# Mixer.net
KiCad netlist of a schematic drawn in EAGLE
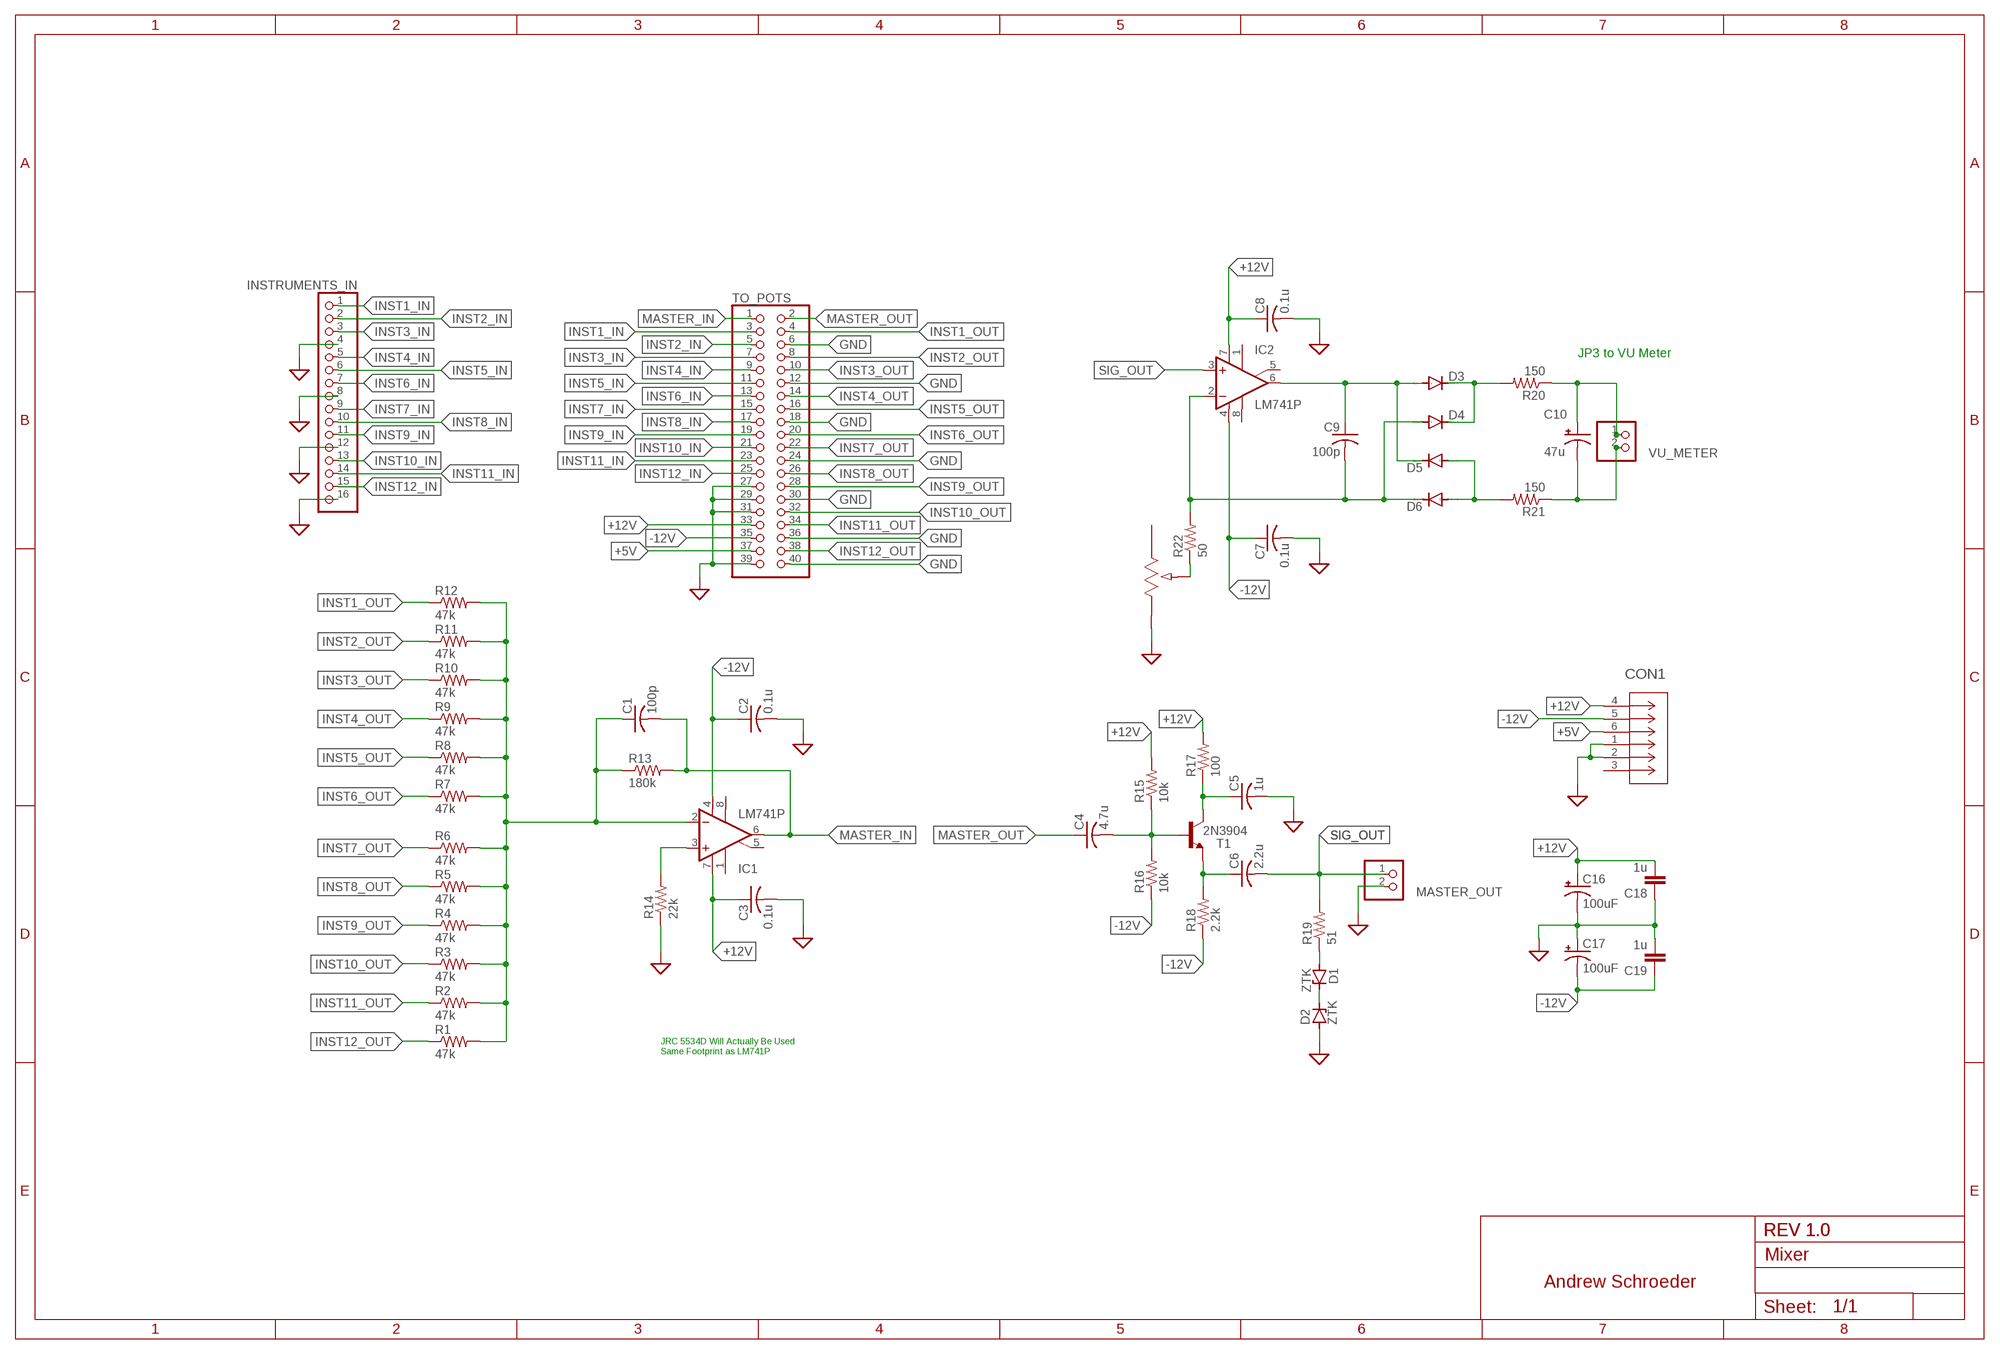
[diagram p0: schematic, sheet 1]

(export (version "E")
  (design (tool "Eeschema 10.0.6"))
  (components
    (comp (ref "C1")
      (value "100p")
      (footprint "eagle-import:C025-025X050")
      (libsource (lib "eagle-import") (part "C-US025-025X050"))
    )
    (comp (ref "C2")
      (value "0.1u")
      (footprint "eagle-import:C025-025X050")
      (libsource (lib "eagle-import") (part "C-US025-025X050"))
    )
    (comp (ref "C3")
      (value "0.1u")
      (footprint "eagle-import:C025-025X050")
      (libsource (lib "eagle-import") (part "C-US025-025X050"))
    )
    (comp (ref "C4")
      (value "4.7u")
      (footprint "eagle-import:C025-025X050")
      (libsource (lib "eagle-import") (part "C-US025-025X050"))
    )
    (comp (ref "C5")
      (value "1u")
      (footprint "eagle-import:C025-025X050")
      (libsource (lib "eagle-import") (part "C-US025-025X050"))
    )
    (comp (ref "C6")
      (value "2.2u")
      (footprint "eagle-import:C025-025X050")
      (libsource (lib "eagle-import") (part "C-US025-025X050"))
    )
    (comp (ref "C7")
      (value "0.1u")
      (footprint "eagle-import:C025-025X050")
      (libsource (lib "eagle-import") (part "C-US025-025X050"))
    )
    (comp (ref "C8")
      (value "0.1u")
      (footprint "eagle-import:C025-025X050")
      (libsource (lib "eagle-import") (part "C-US025-025X050"))
    )
    (comp (ref "C9")
      (value "100p")
      (footprint "eagle-import:C025-025X050")
      (libsource (lib "eagle-import") (part "C-US025-025X050"))
    )
    (comp (ref "C10")
      (value "47u")
      (footprint "eagle-import:E2-5")
      (libsource (lib "eagle-import") (part "CPOL-USE2-5"))
    )
    (comp (ref "C16")
      (value "100uF")
      (footprint "eagle-import:E5-8,5")
      (libsource (lib "eagle-import") (part "CPOL-USE5-8.5"))
    )
    (comp (ref "C17")
      (value "100uF")
      (footprint "eagle-import:E5-8,5")
      (libsource (lib "eagle-import") (part "CPOL-USE5-8.5"))
    )
    (comp (ref "C18")
      (value "1u")
      (footprint "eagle-import:C050-024X044")
      (libsource (lib "eagle-import") (part "C-EU050-024X044"))
    )
    (comp (ref "C19")
      (value "1u")
      (footprint "eagle-import:C050-024X044")
      (libsource (lib "eagle-import") (part "C-EU050-024X044"))
    )
    (comp (ref "CON1")
      (value "1-770875-01-770875-0_VERTICAL")
      (footprint "eagle-import:1-770875-0")
      (libsource (lib "eagle-import") (part "1-770875-01-770875-0_VERTICAL"))
    )
    (comp (ref "D1")
      (value "ZTK")
      (footprint "eagle-import:DO35Z10")
      (libsource (lib "eagle-import") (part "ZTK"))
    )
    (comp (ref "D2")
      (value "ZTK")
      (footprint "eagle-import:DO35Z10")
      (libsource (lib "eagle-import") (part "ZTK"))
    )
    (comp (ref "D3")
      (value "1N4148DO35-7")
      (footprint "eagle-import:DO35-7")
      (libsource (lib "eagle-import") (part "1N4148DO35-7"))
    )
    (comp (ref "D4")
      (value "1N4148DO35-7")
      (footprint "eagle-import:DO35-7")
      (libsource (lib "eagle-import") (part "1N4148DO35-7"))
    )
    (comp (ref "D5")
      (value "1N4148DO35-7")
      (footprint "eagle-import:DO35-7")
      (libsource (lib "eagle-import") (part "1N4148DO35-7"))
    )
    (comp (ref "D6")
      (value "1N4148DO35-7")
      (footprint "eagle-import:DO35-7")
      (libsource (lib "eagle-import") (part "1N4148DO35-7"))
    )
    (comp (ref "IC1")
      (value "LM741P")
      (footprint "eagle-import:DIL08")
      (libsource (lib "eagle-import") (part "741PLM"))
    )
    (comp (ref "IC2")
      (value "LM741P")
      (footprint "eagle-import:DIL08")
      (libsource (lib "eagle-import") (part "741PLM"))
    )
    (comp (ref "INSTRUMENTS_IN")
      (value "PINHD-1X16")
      (footprint "eagle-import:1X16")
      (libsource (lib "eagle-import") (part "PINHD-1X16"))
    )
    (comp (ref "MASTER_OUT")
      (value "PINHD-1X2")
      (footprint "eagle-import:1X02")
      (libsource (lib "eagle-import") (part "PINHD-1X2"))
    )
    (comp (ref "R1")
      (value "47k")
      (footprint "eagle-import:0207_7")
      (libsource (lib "eagle-import") (part "R-US_0207/7"))
    )
    (comp (ref "R2")
      (value "47k")
      (footprint "eagle-import:0207_7")
      (libsource (lib "eagle-import") (part "R-US_0207/7"))
    )
    (comp (ref "R3")
      (value "47k")
      (footprint "eagle-import:0207_7")
      (libsource (lib "eagle-import") (part "R-US_0207/7"))
    )
    (comp (ref "R4")
      (value "47k")
      (footprint "eagle-import:0207_7")
      (libsource (lib "eagle-import") (part "R-US_0207/7"))
    )
    (comp (ref "R5")
      (value "47k")
      (footprint "eagle-import:0207_7")
      (libsource (lib "eagle-import") (part "R-US_0207/7"))
    )
    (comp (ref "R6")
      (value "47k")
      (footprint "eagle-import:0207_7")
      (libsource (lib "eagle-import") (part "R-US_0207/7"))
    )
    (comp (ref "R7")
      (value "47k")
      (footprint "eagle-import:0207_7")
      (libsource (lib "eagle-import") (part "R-US_0207/7"))
    )
    (comp (ref "R8")
      (value "47k")
      (footprint "eagle-import:0207_7")
      (libsource (lib "eagle-import") (part "R-US_0207/7"))
    )
    (comp (ref "R9")
      (value "47k")
      (footprint "eagle-import:0207_7")
      (libsource (lib "eagle-import") (part "R-US_0207/7"))
    )
    (comp (ref "R10")
      (value "47k")
      (footprint "eagle-import:0207_7")
      (libsource (lib "eagle-import") (part "R-US_0207/7"))
    )
    (comp (ref "R11")
      (value "47k")
      (footprint "eagle-import:0207_7")
      (libsource (lib "eagle-import") (part "R-US_0207/7"))
    )
    (comp (ref "R12")
      (value "47k")
      (footprint "eagle-import:0207_7")
      (libsource (lib "eagle-import") (part "R-US_0207/7"))
    )
    (comp (ref "R13")
      (value "180k")
      (footprint "eagle-import:0207_7")
      (libsource (lib "eagle-import") (part "R-US_0207/7"))
    )
    (comp (ref "R14")
      (value "22k")
      (footprint "eagle-import:0207_7")
      (libsource (lib "eagle-import") (part "R-US_0207/7"))
    )
    (comp (ref "R15")
      (value "10k")
      (footprint "eagle-import:0207_7")
      (libsource (lib "eagle-import") (part "R-US_0207/7"))
    )
    (comp (ref "R16")
      (value "10k")
      (footprint "eagle-import:0207_7")
      (libsource (lib "eagle-import") (part "R-US_0207/7"))
    )
    (comp (ref "R17")
      (value "100")
      (footprint "eagle-import:0207_7")
      (libsource (lib "eagle-import") (part "R-US_0207/7"))
    )
    (comp (ref "R18")
      (value "2.2k")
      (footprint "eagle-import:0207_7")
      (libsource (lib "eagle-import") (part "R-US_0207/7"))
    )
    (comp (ref "R19")
      (value "51")
      (footprint "eagle-import:0207_7")
      (libsource (lib "eagle-import") (part "R-US_0207/7"))
    )
    (comp (ref "R20")
      (value "150")
      (footprint "eagle-import:0207_7")
      (libsource (lib "eagle-import") (part "R-US_0207/7"))
    )
    (comp (ref "R21")
      (value "150")
      (footprint "eagle-import:0207_7")
      (libsource (lib "eagle-import") (part "R-US_0207/7"))
    )
    (comp (ref "R22")
      (value "50")
      (footprint "eagle-import:0207_7")
      (libsource (lib "eagle-import") (part "R-US_0207/7"))
    )
    (comp (ref "R23")
      (value "PV36W101C01B00")
      (footprint "eagle-import:POT_PV36W")
      (libsource (lib "eagle-import") (part "PV36W101C01B00"))
    )
    (comp (ref "T1")
      (value "2N3904")
      (footprint "eagle-import:TO92")
      (libsource (lib "eagle-import") (part "2N3904"))
    )
    (comp (ref "TO_POTS")
      (value "PINHD-2X20")
      (footprint "eagle-import:2X20")
      (libsource (lib "eagle-import") (part "PINHD-2X20"))
    )
    (comp (ref "VU_METER")
      (value "PINHD-1X2")
      (footprint "eagle-import:1X02")
      (libsource (lib "eagle-import") (part "PINHD-1X2"))
    )
  )
  (nets
    (net (code "1") (name "+5V") (class "Default")
      (node (ref "CON1") (pin "6") (pinfunction "3_6") (pintype "passive"))
      (node (ref "TO_POTS") (pin "37") (pinfunction "37_37") (pintype "passive"))
    )
    (net (code "2") (name "+12V") (class "Default")
      (node (ref "C16") (pin "+") (pinfunction "+_+") (pintype "passive"))
      (node (ref "C18") (pin "2") (pinfunction "2_2") (pintype "passive"))
      (node (ref "C3") (pin "1") (pinfunction "1_1") (pintype "passive"))
      (node (ref "C8") (pin "1") (pinfunction "1_1") (pintype "passive"))
      (node (ref "CON1") (pin "4") (pinfunction "1_4") (pintype "passive"))
      (node (ref "IC1") (pin "7") (pinfunction "V+_7") (pintype "power_in"))
      (node (ref "IC2") (pin "7") (pinfunction "V+_7") (pintype "power_in"))
      (node (ref "R15") (pin "2") (pinfunction "2_2") (pintype "passive"))
      (node (ref "R17") (pin "2") (pinfunction "2_2") (pintype "passive"))
      (node (ref "TO_POTS") (pin "33") (pinfunction "33_33") (pintype "passive"))
    )
    (net (code "3") (name "-12V") (class "Default")
      (node (ref "C17") (pin "-") (pinfunction "-_-") (pintype "passive"))
      (node (ref "C19") (pin "1") (pinfunction "1_1") (pintype "passive"))
      (node (ref "C2") (pin "1") (pinfunction "1_1") (pintype "passive"))
      (node (ref "C7") (pin "1") (pinfunction "1_1") (pintype "passive"))
      (node (ref "CON1") (pin "5") (pinfunction "2_5") (pintype "passive"))
      (node (ref "IC1") (pin "4") (pinfunction "V-_4") (pintype "power_in"))
      (node (ref "IC2") (pin "4") (pinfunction "V-_4") (pintype "power_in"))
      (node (ref "R16") (pin "1") (pinfunction "1_1") (pintype "passive"))
      (node (ref "R18") (pin "1") (pinfunction "1_1") (pintype "passive"))
      (node (ref "TO_POTS") (pin "35") (pinfunction "35_35") (pintype "passive"))
    )
    (net (code "4") (name "GND") (class "Default")
      (node (ref "C16") (pin "-") (pinfunction "-_-") (pintype "passive"))
      (node (ref "C17") (pin "+") (pinfunction "+_+") (pintype "passive"))
      (node (ref "C18") (pin "1") (pinfunction "1_1") (pintype "passive"))
      (node (ref "C19") (pin "2") (pinfunction "2_2") (pintype "passive"))
      (node (ref "C2") (pin "2") (pinfunction "2_2") (pintype "passive"))
      (node (ref "C3") (pin "2") (pinfunction "2_2") (pintype "passive"))
      (node (ref "C5") (pin "2") (pinfunction "2_2") (pintype "passive"))
      (node (ref "C7") (pin "2") (pinfunction "2_2") (pintype "passive"))
      (node (ref "C8") (pin "2") (pinfunction "2_2") (pintype "passive"))
      (node (ref "CON1") (pin "1") (pinfunction "4_1") (pintype "passive"))
      (node (ref "CON1") (pin "2") (pinfunction "5_2") (pintype "passive"))
      (node (ref "D2") (pin "A") (pinfunction "A_A") (pintype "passive"))
      (node (ref "INSTRUMENTS_IN") (pin "12") (pinfunction "12_12") (pintype "passive"))
      (node (ref "INSTRUMENTS_IN") (pin "16") (pinfunction "16_16") (pintype "passive"))
      (node (ref "INSTRUMENTS_IN") (pin "4") (pinfunction "4_4") (pintype "passive"))
      (node (ref "INSTRUMENTS_IN") (pin "8") (pinfunction "8_8") (pintype "passive"))
      (node (ref "MASTER_OUT") (pin "2") (pinfunction "2_2") (pintype "passive"))
      (node (ref "R14") (pin "1") (pinfunction "1_1") (pintype "passive"))
      (node (ref "R23") (pin "3") (pinfunction "3_3") (pintype "passive"))
      (node (ref "TO_POTS") (pin "12") (pinfunction "12_12") (pintype "passive"))
      (node (ref "TO_POTS") (pin "18") (pinfunction "18_18") (pintype "passive"))
      (node (ref "TO_POTS") (pin "24") (pinfunction "24_24") (pintype "passive"))
      (node (ref "TO_POTS") (pin "27") (pinfunction "27_27") (pintype "passive"))
      (node (ref "TO_POTS") (pin "29") (pinfunction "29_29") (pintype "passive"))
      (node (ref "TO_POTS") (pin "30") (pinfunction "30_30") (pintype "passive"))
      (node (ref "TO_POTS") (pin "31") (pinfunction "31_31") (pintype "passive"))
      (node (ref "TO_POTS") (pin "36") (pinfunction "36_36") (pintype "passive"))
      (node (ref "TO_POTS") (pin "39") (pinfunction "39_39") (pintype "passive"))
      (node (ref "TO_POTS") (pin "40") (pinfunction "40_40") (pintype "passive"))
      (node (ref "TO_POTS") (pin "6") (pinfunction "6_6") (pintype "passive"))
    )
    (net (code "5") (name "INST1_IN") (class "Default")
      (node (ref "INSTRUMENTS_IN") (pin "1") (pinfunction "1_1") (pintype "passive"))
      (node (ref "TO_POTS") (pin "3") (pinfunction "3_3") (pintype "passive"))
    )
    (net (code "6") (name "INST1_OUT") (class "Default")
      (node (ref "R12") (pin "1") (pinfunction "1_1") (pintype "passive"))
      (node (ref "TO_POTS") (pin "4") (pinfunction "4_4") (pintype "passive"))
    )
    (net (code "7") (name "INST2_IN") (class "Default")
      (node (ref "INSTRUMENTS_IN") (pin "2") (pinfunction "2_2") (pintype "passive"))
      (node (ref "TO_POTS") (pin "5") (pinfunction "5_5") (pintype "passive"))
    )
    (net (code "8") (name "INST2_OUT") (class "Default")
      (node (ref "R11") (pin "1") (pinfunction "1_1") (pintype "passive"))
      (node (ref "TO_POTS") (pin "8") (pinfunction "8_8") (pintype "passive"))
    )
    (net (code "9") (name "INST3_IN") (class "Default")
      (node (ref "INSTRUMENTS_IN") (pin "3") (pinfunction "3_3") (pintype "passive"))
      (node (ref "TO_POTS") (pin "7") (pinfunction "7_7") (pintype "passive"))
    )
    (net (code "10") (name "INST3_OUT") (class "Default")
      (node (ref "R10") (pin "1") (pinfunction "1_1") (pintype "passive"))
      (node (ref "TO_POTS") (pin "10") (pinfunction "10_10") (pintype "passive"))
    )
    (net (code "11") (name "INST4_IN") (class "Default")
      (node (ref "INSTRUMENTS_IN") (pin "5") (pinfunction "5_5") (pintype "passive"))
      (node (ref "TO_POTS") (pin "9") (pinfunction "9_9") (pintype "passive"))
    )
    (net (code "12") (name "INST4_OUT") (class "Default")
      (node (ref "R9") (pin "1") (pinfunction "1_1") (pintype "passive"))
      (node (ref "TO_POTS") (pin "14") (pinfunction "14_14") (pintype "passive"))
    )
    (net (code "13") (name "INST5_IN") (class "Default")
      (node (ref "INSTRUMENTS_IN") (pin "6") (pinfunction "6_6") (pintype "passive"))
      (node (ref "TO_POTS") (pin "11") (pinfunction "11_11") (pintype "passive"))
    )
    (net (code "14") (name "INST5_OUT") (class "Default")
      (node (ref "R8") (pin "1") (pinfunction "1_1") (pintype "passive"))
      (node (ref "TO_POTS") (pin "16") (pinfunction "16_16") (pintype "passive"))
    )
    (net (code "15") (name "INST6_IN") (class "Default")
      (node (ref "INSTRUMENTS_IN") (pin "7") (pinfunction "7_7") (pintype "passive"))
      (node (ref "TO_POTS") (pin "13") (pinfunction "13_13") (pintype "passive"))
    )
    (net (code "16") (name "INST6_OUT") (class "Default")
      (node (ref "R7") (pin "1") (pinfunction "1_1") (pintype "passive"))
      (node (ref "TO_POTS") (pin "20") (pinfunction "20_20") (pintype "passive"))
    )
    (net (code "17") (name "INST7_IN") (class "Default")
      (node (ref "INSTRUMENTS_IN") (pin "9") (pinfunction "9_9") (pintype "passive"))
      (node (ref "TO_POTS") (pin "15") (pinfunction "15_15") (pintype "passive"))
    )
    (net (code "18") (name "INST7_OUT") (class "Default")
      (node (ref "R6") (pin "1") (pinfunction "1_1") (pintype "passive"))
      (node (ref "TO_POTS") (pin "22") (pinfunction "22_22") (pintype "passive"))
    )
    (net (code "19") (name "INST8_IN") (class "Default")
      (node (ref "INSTRUMENTS_IN") (pin "10") (pinfunction "10_10") (pintype "passive"))
      (node (ref "TO_POTS") (pin "17") (pinfunction "17_17") (pintype "passive"))
    )
    (net (code "20") (name "INST8_OUT") (class "Default")
      (node (ref "R5") (pin "1") (pinfunction "1_1") (pintype "passive"))
      (node (ref "TO_POTS") (pin "26") (pinfunction "26_26") (pintype "passive"))
    )
    (net (code "21") (name "INST9_IN") (class "Default")
      (node (ref "INSTRUMENTS_IN") (pin "11") (pinfunction "11_11") (pintype "passive"))
      (node (ref "TO_POTS") (pin "19") (pinfunction "19_19") (pintype "passive"))
    )
    (net (code "22") (name "INST9_OUT") (class "Default")
      (node (ref "R4") (pin "1") (pinfunction "1_1") (pintype "passive"))
      (node (ref "TO_POTS") (pin "28") (pinfunction "28_28") (pintype "passive"))
    )
    (net (code "23") (name "INST10_IN") (class "Default")
      (node (ref "INSTRUMENTS_IN") (pin "13") (pinfunction "13_13") (pintype "passive"))
      (node (ref "TO_POTS") (pin "21") (pinfunction "21_21") (pintype "passive"))
    )
    (net (code "24") (name "INST10_OUT") (class "Default")
      (node (ref "R3") (pin "1") (pinfunction "1_1") (pintype "passive"))
      (node (ref "TO_POTS") (pin "32") (pinfunction "32_32") (pintype "passive"))
    )
    (net (code "25") (name "INST11_IN") (class "Default")
      (node (ref "INSTRUMENTS_IN") (pin "14") (pinfunction "14_14") (pintype "passive"))
      (node (ref "TO_POTS") (pin "23") (pinfunction "23_23") (pintype "passive"))
    )
    (net (code "26") (name "INST11_OUT") (class "Default")
      (node (ref "R2") (pin "1") (pinfunction "1_1") (pintype "passive"))
      (node (ref "TO_POTS") (pin "34") (pinfunction "34_34") (pintype "passive"))
    )
    (net (code "27") (name "INST12_IN") (class "Default")
      (node (ref "INSTRUMENTS_IN") (pin "15") (pinfunction "15_15") (pintype "passive"))
      (node (ref "TO_POTS") (pin "25") (pinfunction "25_25") (pintype "passive"))
    )
    (net (code "28") (name "INST12_OUT") (class "Default")
      (node (ref "R1") (pin "1") (pinfunction "1_1") (pintype "passive"))
      (node (ref "TO_POTS") (pin "38") (pinfunction "38_38") (pintype "passive"))
    )
    (net (code "29") (name "MASTER_IN") (class "Default")
      (node (ref "C1") (pin "2") (pinfunction "2_2") (pintype "passive"))
      (node (ref "IC1") (pin "6") (pinfunction "OUT_6") (pintype "output"))
      (node (ref "R13") (pin "2") (pinfunction "2_2") (pintype "passive"))
      (node (ref "TO_POTS") (pin "1") (pinfunction "1_1") (pintype "passive"))
    )
    (net (code "30") (name "MASTER_OUT") (class "Default")
      (node (ref "C4") (pin "1") (pinfunction "1_1") (pintype "passive"))
      (node (ref "TO_POTS") (pin "2") (pinfunction "2_2") (pintype "passive"))
    )
    (net (code "31") (name "Net-(C10-Pad+)") (class "Default")
      (node (ref "C10") (pin "+") (pinfunction "+_+") (pintype "passive"))
      (node (ref "R20") (pin "1") (pinfunction "1_1") (pintype "passive"))
      (node (ref "VU_METER") (pin "1") (pinfunction "1_1") (pintype "passive"))
    )
    (net (code "32") (name "Net-(C10-Pad-)") (class "Default")
      (node (ref "C10") (pin "-") (pinfunction "-_-") (pintype "passive"))
      (node (ref "R21") (pin "1") (pinfunction "1_1") (pintype "passive"))
      (node (ref "VU_METER") (pin "2") (pinfunction "2_2") (pintype "passive"))
    )
    (net (code "33") (name "Net-(D1-PadA)") (class "Default")
      (node (ref "D1") (pin "A") (pinfunction "A_A") (pintype "passive"))
      (node (ref "R19") (pin "1") (pinfunction "1_1") (pintype "passive"))
    )
    (net (code "34") (name "Net-(D1-PadC)") (class "Default")
      (node (ref "D1") (pin "C") (pinfunction "C_C") (pintype "passive"))
      (node (ref "D2") (pin "C") (pinfunction "C_C") (pintype "passive"))
    )
    (net (code "35") (name "Net-(D3-PadC)") (class "Default")
      (node (ref "D3") (pin "C") (pinfunction "C_C") (pintype "passive"))
      (node (ref "D4") (pin "C") (pinfunction "C_C") (pintype "passive"))
      (node (ref "R20") (pin "2") (pinfunction "2_2") (pintype "passive"))
    )
    (net (code "36") (name "Net-(D5-PadA)") (class "Default")
      (node (ref "D5") (pin "A") (pinfunction "A_A") (pintype "passive"))
      (node (ref "D6") (pin "A") (pinfunction "A_A") (pintype "passive"))
      (node (ref "R21") (pin "2") (pinfunction "2_2") (pintype "passive"))
    )
    (net (code "37") (name "Net-(IC1-+IN)") (class "Default")
      (node (ref "IC1") (pin "3") (pinfunction "+IN_3") (pintype "input"))
      (node (ref "R14") (pin "2") (pinfunction "2_2") (pintype "passive"))
    )
    (net (code "38") (name "Net-(IC1--IN)") (class "Default")
      (node (ref "C1") (pin "1") (pinfunction "1_1") (pintype "passive"))
      (node (ref "IC1") (pin "2") (pinfunction "-IN_2") (pintype "input"))
      (node (ref "R1") (pin "2") (pinfunction "2_2") (pintype "passive"))
      (node (ref "R10") (pin "2") (pinfunction "2_2") (pintype "passive"))
      (node (ref "R11") (pin "2") (pinfunction "2_2") (pintype "passive"))
      (node (ref "R12") (pin "2") (pinfunction "2_2") (pintype "passive"))
      (node (ref "R13") (pin "1") (pinfunction "1_1") (pintype "passive"))
      (node (ref "R2") (pin "2") (pinfunction "2_2") (pintype "passive"))
      (node (ref "R3") (pin "2") (pinfunction "2_2") (pintype "passive"))
      (node (ref "R4") (pin "2") (pinfunction "2_2") (pintype "passive"))
      (node (ref "R5") (pin "2") (pinfunction "2_2") (pintype "passive"))
      (node (ref "R6") (pin "2") (pinfunction "2_2") (pintype "passive"))
      (node (ref "R7") (pin "2") (pinfunction "2_2") (pintype "passive"))
      (node (ref "R8") (pin "2") (pinfunction "2_2") (pintype "passive"))
      (node (ref "R9") (pin "2") (pinfunction "2_2") (pintype "passive"))
    )
    (net (code "39") (name "Net-(IC2--IN)") (class "Default")
      (node (ref "C9") (pin "2") (pinfunction "2_2") (pintype "passive"))
      (node (ref "D4") (pin "A") (pinfunction "A_A") (pintype "passive"))
      (node (ref "D6") (pin "C") (pinfunction "C_C") (pintype "passive"))
      (node (ref "IC2") (pin "2") (pinfunction "-IN_2") (pintype "input"))
      (node (ref "R22") (pin "2") (pinfunction "2_2") (pintype "passive"))
    )
    (net (code "40") (name "Net-(IC2-OUT)") (class "Default")
      (node (ref "C9") (pin "1") (pinfunction "1_1") (pintype "passive"))
      (node (ref "D3") (pin "A") (pinfunction "A_A") (pintype "passive"))
      (node (ref "D5") (pin "C") (pinfunction "C_C") (pintype "passive"))
      (node (ref "IC2") (pin "6") (pinfunction "OUT_6") (pintype "output"))
    )
    (net (code "41") (name "Net-(R22-Pad1)") (class "Default")
      (node (ref "R22") (pin "1") (pinfunction "1_1") (pintype "passive"))
      (node (ref "R23") (pin "2") (pinfunction "2_2") (pintype "passive"))
    )
    (net (code "42") (name "Net-(T1-B)") (class "Default")
      (node (ref "C4") (pin "2") (pinfunction "2_2") (pintype "passive"))
      (node (ref "R15") (pin "1") (pinfunction "1_1") (pintype "passive"))
      (node (ref "R16") (pin "2") (pinfunction "2_2") (pintype "passive"))
      (node (ref "T1") (pin "2") (pinfunction "B_2") (pintype "passive"))
    )
    (net (code "43") (name "Net-(T1-C)") (class "Default")
      (node (ref "C5") (pin "1") (pinfunction "1_1") (pintype "passive"))
      (node (ref "R17") (pin "1") (pinfunction "1_1") (pintype "passive"))
      (node (ref "T1") (pin "1") (pinfunction "C_1") (pintype "passive"))
    )
    (net (code "44") (name "Net-(T1-E)") (class "Default")
      (node (ref "C6") (pin "1") (pinfunction "1_1") (pintype "passive"))
      (node (ref "R18") (pin "2") (pinfunction "2_2") (pintype "passive"))
      (node (ref "T1") (pin "3") (pinfunction "E_3") (pintype "passive"))
    )
    (net (code "45") (name "SIG_OUT") (class "Default")
      (node (ref "C6") (pin "2") (pinfunction "2_2") (pintype "passive"))
      (node (ref "IC2") (pin "3") (pinfunction "+IN_3") (pintype "input"))
      (node (ref "MASTER_OUT") (pin "1") (pinfunction "1_1") (pintype "passive"))
      (node (ref "R19") (pin "2") (pinfunction "2_2") (pintype "passive"))
    )
    (net (code "46") (name "unconnected-(CON1-6-Pad3)") (class "Default")
      (node (ref "CON1") (pin "3") (pinfunction "6_3") (pintype "passive"))
    )
    (net (code "47") (name "unconnected-(IC1-ON1-Pad1)") (class "Default")
      (node (ref "IC1") (pin "1") (pinfunction "ON1_1") (pintype "passive"))
    )
    (net (code "48") (name "unconnected-(IC1-ON2-Pad5)") (class "Default")
      (node (ref "IC1") (pin "5") (pinfunction "ON2_5") (pintype "passive"))
    )
    (net (code "49") (name "unconnected-(IC1-OPT-Pad8)") (class "Default")
      (node (ref "IC1") (pin "8") (pinfunction "OPT_8") (pintype "passive"))
    )
    (net (code "50") (name "unconnected-(IC2-ON1-Pad1)") (class "Default")
      (node (ref "IC2") (pin "1") (pinfunction "ON1_1") (pintype "passive"))
    )
    (net (code "51") (name "unconnected-(IC2-ON2-Pad5)") (class "Default")
      (node (ref "IC2") (pin "5") (pinfunction "ON2_5") (pintype "passive"))
    )
    (net (code "52") (name "unconnected-(IC2-OPT-Pad8)") (class "Default")
      (node (ref "IC2") (pin "8") (pinfunction "OPT_8") (pintype "passive"))
    )
    (net (code "53") (name "unconnected-(R23-Pad1)") (class "Default")
      (node (ref "R23") (pin "1") (pinfunction "1_1") (pintype "passive"))
    )
  )
)
